# MagicBeater.net
KiCad netlist of a schematic drawn in EAGLE
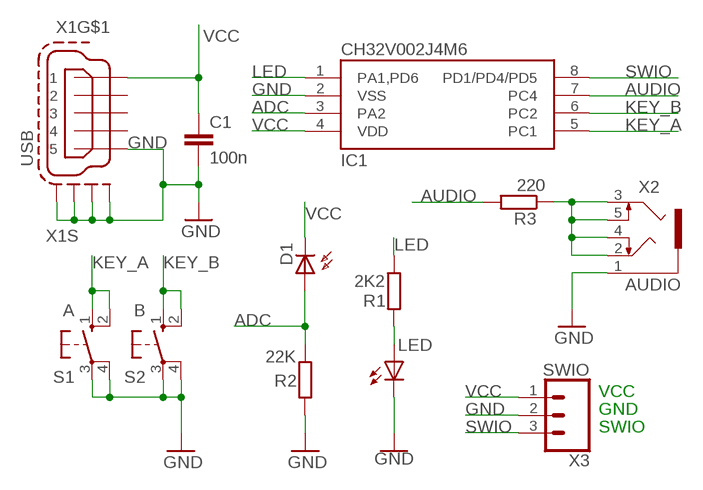
[diagram p0: schematic, sheet 1]

(export (version "E")
  (design (tool "Eeschema 10.0.6"))
  (components
    (comp (ref "C1")
      (value "100n")
      (footprint "eagle-import:C050-024X044")
      (libsource (lib "eagle-import") (part "C-EU050-024X044"))
    )
    (comp (ref "D1")
      (value "BPW32")
      (footprint "eagle-import:BPW32")
      (libsource (lib "eagle-import") (part "BPW32"))
    )
    (comp (ref "IC1")
      (value "CH32V002J4M6")
      (footprint "eagle-import:SOP8")
      (libsource (lib "eagle-import") (part "CH32V003J4M6"))
    )
    (comp (ref "LED")
      (value "LEDLED5MMB")
      (footprint "eagle-import:LED5MMB")
      (libsource (lib "eagle-import") (part "LEDLED5MMB"))
    )
    (comp (ref "R1")
      (value "2K2")
      (footprint "eagle-import:0204_7")
      (libsource (lib "eagle-import") (part "R-EU_0204/7"))
    )
    (comp (ref "R2")
      (value "22K")
      (footprint "eagle-import:0204_7")
      (libsource (lib "eagle-import") (part "R-EU_0204/7"))
    )
    (comp (ref "R3")
      (value "220")
      (footprint "eagle-import:0204_7")
      (libsource (lib "eagle-import") (part "R-EU_0204/7"))
    )
    (comp (ref "S1")
      (value "A")
      (footprint "eagle-import:B3F-10XX")
      (fields (field (name "MPN") "B3F-1000"))
      (libsource (lib "eagle-import") (part "10-XX"))
    )
    (comp (ref "S2")
      (value "B")
      (footprint "eagle-import:B3F-10XX")
      (fields (field (name "MPN") "B3F-1000"))
      (libsource (lib "eagle-import") (part "10-XX"))
    )
    (comp (ref "X1")
      (value "USB")
      (footprint "eagle-import:32005-201")
      (libsource (lib "eagle-import") (part "MINI-USB-SCHIELD-32005-201"))
    )
    (comp (ref "X2")
      (value "AUDIO")
      (footprint "eagle-import:1503_09")
      (libsource (lib "eagle-import") (part "1503_09"))
    )
    (comp (ref "X3")
      (value "SWIO")
      (footprint "eagle-import:1X03_LONGPADS")
      (libsource (lib "eagle-import") (part "CONN_03LONGPADS"))
    )
  )
  (nets
    (net (code "1") (name "/ADC") (class "Default")
      (node (ref "D1") (pin "A") (pinfunction "A_A") (pintype "passive"))
      (node (ref "IC1") (pin "3") (pinfunction "PA2_3") (pintype "bidirectional"))
      (node (ref "R2") (pin "1") (pinfunction "1_1") (pintype "passive"))
    )
    (net (code "2") (name "/AUDIO") (class "Default")
      (node (ref "IC1") (pin "7") (pinfunction "PC4_7") (pintype "bidirectional"))
      (node (ref "R3") (pin "2") (pinfunction "2_2") (pintype "passive"))
    )
    (net (code "3") (name "/KEY_A") (class "Default")
      (node (ref "IC1") (pin "5") (pinfunction "PC1_5") (pintype "bidirectional"))
      (node (ref "S1") (pin "1") (pinfunction "S_1") (pintype "passive"))
      (node (ref "S1") (pin "2") (pinfunction "S1_2") (pintype "passive"))
    )
    (net (code "4") (name "/KEY_B") (class "Default")
      (node (ref "IC1") (pin "6") (pinfunction "PC2_6") (pintype "bidirectional"))
      (node (ref "S2") (pin "1") (pinfunction "S_1") (pintype "passive"))
      (node (ref "S2") (pin "2") (pinfunction "S1_2") (pintype "passive"))
    )
    (net (code "5") (name "/LED") (class "Default")
      (node (ref "IC1") (pin "1") (pinfunction "PA1,PD6_1") (pintype "bidirectional"))
      (node (ref "R1") (pin "1") (pinfunction "1_1") (pintype "passive"))
    )
    (net (code "6") (name "/SWIO") (class "Default")
      (node (ref "IC1") (pin "8") (pinfunction "PD1/PD4/PD5_8") (pintype "bidirectional"))
      (node (ref "X3") (pin "3") (pinfunction "3_3") (pintype "passive"))
    )
    (net (code "7") (name "/VCC") (class "Default")
      (node (ref "C1") (pin "1") (pinfunction "1_1") (pintype "passive"))
      (node (ref "D1") (pin "K") (pinfunction "C_K") (pintype "passive"))
      (node (ref "IC1") (pin "4") (pinfunction "VDD_4") (pintype "power_in"))
      (node (ref "X1") (pin "1") (pinfunction "1_1") (pintype "passive"))
      (node (ref "X3") (pin "1") (pinfunction "1_1") (pintype "passive"))
    )
    (net (code "8") (name "GND") (class "Default")
      (node (ref "C1") (pin "2") (pinfunction "2_2") (pintype "passive"))
      (node (ref "IC1") (pin "2") (pinfunction "VSS_2") (pintype "power_in"))
      (node (ref "LED") (pin "K") (pinfunction "C_K") (pintype "passive"))
      (node (ref "R2") (pin "2") (pinfunction "2_2") (pintype "passive"))
      (node (ref "S1") (pin "3") (pinfunction "P_3") (pintype "passive"))
      (node (ref "S1") (pin "4") (pinfunction "P1_4") (pintype "passive"))
      (node (ref "S2") (pin "3") (pinfunction "P_3") (pintype "passive"))
      (node (ref "S2") (pin "4") (pinfunction "P1_4") (pintype "passive"))
      (node (ref "X1") (pin "5") (pinfunction "5_5") (pintype "passive"))
      (node (ref "X1") (pin "M1") (pinfunction "S1_M1") (pintype "passive"))
      (node (ref "X1") (pin "M2") (pinfunction "S2_M2") (pintype "passive"))
      (node (ref "X1") (pin "M3") (pinfunction "S3_M3") (pintype "passive"))
      (node (ref "X1") (pin "M4") (pinfunction "S4_M4") (pintype "passive"))
      (node (ref "X2") (pin "1") (pinfunction "1_1") (pintype "passive"))
      (node (ref "X3") (pin "2") (pinfunction "2_2") (pintype "passive"))
    )
    (net (code "9") (name "Net-(LED-PadA)") (class "Default")
      (node (ref "LED") (pin "A") (pinfunction "A_A") (pintype "passive"))
      (node (ref "R1") (pin "2") (pinfunction "2_2") (pintype "passive"))
    )
    (net (code "10") (name "Net-(R3-Pad1)") (class "Default")
      (node (ref "R3") (pin "1") (pinfunction "1_1") (pintype "passive"))
      (node (ref "X2") (pin "2") (pinfunction "2_2") (pintype "passive"))
      (node (ref "X2") (pin "3") (pinfunction "3_3") (pintype "passive"))
      (node (ref "X2") (pin "4") (pinfunction "4_4") (pintype "passive"))
      (node (ref "X2") (pin "5") (pinfunction "5_5") (pintype "passive"))
    )
    (net (code "11") (name "unconnected-(X1-Pad2)") (class "Default")
      (node (ref "X1") (pin "2") (pinfunction "2_2") (pintype "passive"))
    )
    (net (code "12") (name "unconnected-(X1-Pad3)") (class "Default")
      (node (ref "X1") (pin "3") (pinfunction "3_3") (pintype "passive"))
    )
    (net (code "13") (name "unconnected-(X1-Pad4)") (class "Default")
      (node (ref "X1") (pin "4") (pinfunction "4_4") (pintype "passive"))
    )
  )
)
